# 4Bit_Computer_-_2_4Bit_Input.net
KiCad netlist of a schematic drawn in EAGLE
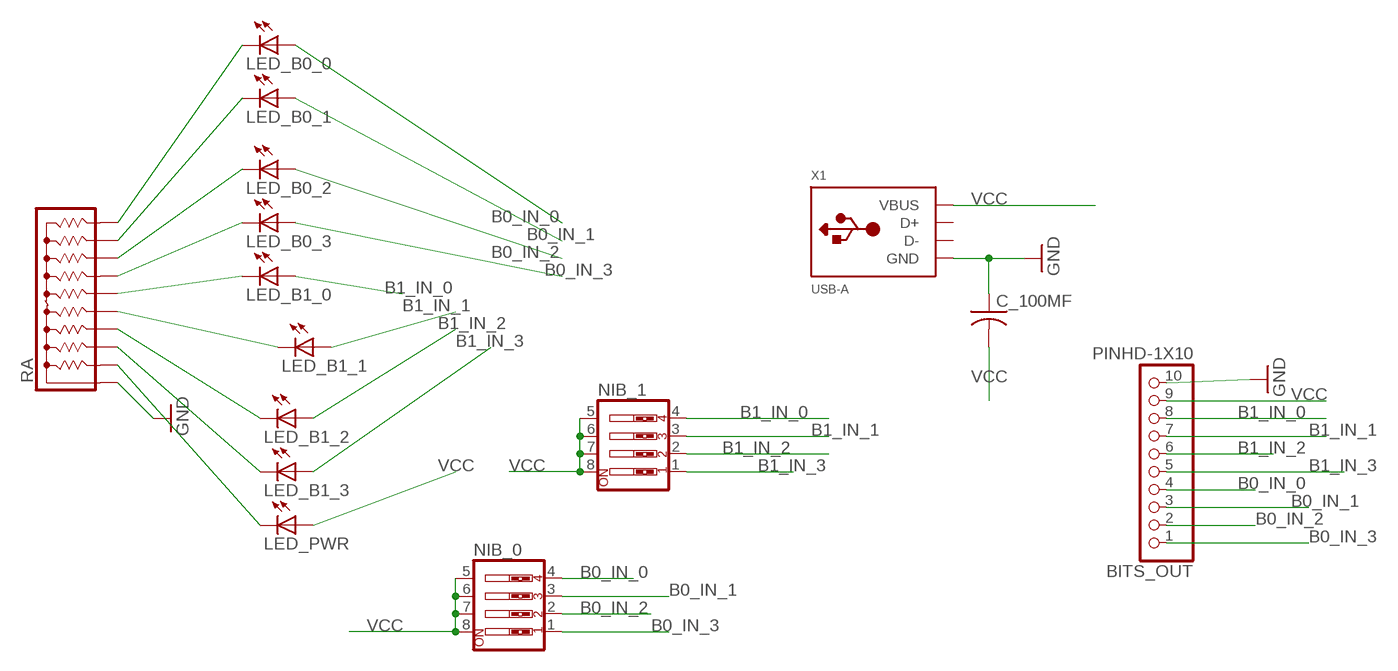
[diagram p0: schematic, sheet 1]

(export (version "E")
  (design (tool "Eeschema 10.0.6"))
  (components
    (comp (ref "BITS_OUT")
      (value "PINHD-1X10")
      (footprint "eagle-import:1X10-BIG")
      (libsource (lib "eagle-import") (part "PINHD-1X10"))
    )
    (comp (ref "C_100MF")
      (value "C-US025-030X050")
      (footprint "eagle-import:C025-030X050")
      (libsource (lib "eagle-import") (part "C-US025-030X050"))
    )
    (comp (ref "LED_B0_0")
      (value "LEDSMT1206")
      (footprint "eagle-import:1206")
      (libsource (lib "eagle-import") (part "LEDSMT1206"))
    )
    (comp (ref "LED_B0_1")
      (value "LEDSMT1206")
      (footprint "eagle-import:1206")
      (libsource (lib "eagle-import") (part "LEDSMT1206"))
    )
    (comp (ref "LED_B0_2")
      (value "LEDSMT1206")
      (footprint "eagle-import:1206")
      (libsource (lib "eagle-import") (part "LEDSMT1206"))
    )
    (comp (ref "LED_B0_3")
      (value "LEDSMT1206")
      (footprint "eagle-import:1206")
      (libsource (lib "eagle-import") (part "LEDSMT1206"))
    )
    (comp (ref "LED_B1_0")
      (value "LEDSMT1206")
      (footprint "eagle-import:1206")
      (libsource (lib "eagle-import") (part "LEDSMT1206"))
    )
    (comp (ref "LED_B1_1")
      (value "LEDSMT1206")
      (footprint "eagle-import:1206")
      (libsource (lib "eagle-import") (part "LEDSMT1206"))
    )
    (comp (ref "LED_B1_2")
      (value "LEDSMT1206")
      (footprint "eagle-import:1206")
      (libsource (lib "eagle-import") (part "LEDSMT1206"))
    )
    (comp (ref "LED_B1_3")
      (value "LEDSMT1206")
      (footprint "eagle-import:1206")
      (libsource (lib "eagle-import") (part "LEDSMT1206"))
    )
    (comp (ref "LED_PWR")
      (value "LEDSMT1206")
      (footprint "eagle-import:1206")
      (libsource (lib "eagle-import") (part "LEDSMT1206"))
    )
    (comp (ref "NIB_0")
      (value "SW_DIP-4")
      (footprint "eagle-import:EDG-04")
      (libsource (lib "eagle-import") (part "SW_DIP-4"))
    )
    (comp (ref "NIB_1")
      (value "SW_DIP-4")
      (footprint "eagle-import:EDG-04")
      (libsource (lib "eagle-import") (part "SW_DIP-4"))
    )
    (comp (ref "RA")
      (value "4610X")
      (footprint "eagle-import:SIP10")
      (libsource (lib "eagle-import") (part "4610X"))
    )
    (comp (ref "X1")
      (value "USB-A")
      (footprint "eagle-import:MOLEX_480371000")
      (libsource (lib "eagle-import") (part "USB-A"))
    )
  )
  (nets
    (net (code "1") (name "/B0_IN_0") (class "Default")
      (node (ref "BITS_OUT") (pin "4") (pinfunction "4_4") (pintype "passive"))
      (node (ref "LED_B0_0") (pin "A") (pinfunction "A_A") (pintype "passive"))
      (node (ref "NIB_0") (pin "4") (pinfunction "4_4") (pintype "passive"))
    )
    (net (code "2") (name "/B0_IN_1") (class "Default")
      (node (ref "BITS_OUT") (pin "3") (pinfunction "3_3") (pintype "passive"))
      (node (ref "LED_B0_1") (pin "A") (pinfunction "A_A") (pintype "passive"))
      (node (ref "NIB_0") (pin "3") (pinfunction "3_3") (pintype "passive"))
    )
    (net (code "3") (name "/B0_IN_2") (class "Default")
      (node (ref "BITS_OUT") (pin "2") (pinfunction "2_2") (pintype "passive"))
      (node (ref "LED_B0_2") (pin "A") (pinfunction "A_A") (pintype "passive"))
      (node (ref "NIB_0") (pin "2") (pinfunction "2_2") (pintype "passive"))
    )
    (net (code "4") (name "/B0_IN_3") (class "Default")
      (node (ref "BITS_OUT") (pin "1") (pinfunction "1_1") (pintype "passive"))
      (node (ref "LED_B0_3") (pin "A") (pinfunction "A_A") (pintype "passive"))
      (node (ref "NIB_0") (pin "1") (pinfunction "1_1") (pintype "passive"))
    )
    (net (code "5") (name "/B1_IN_0") (class "Default")
      (node (ref "BITS_OUT") (pin "8") (pinfunction "8_8") (pintype "passive"))
      (node (ref "LED_B1_0") (pin "A") (pinfunction "A_A") (pintype "passive"))
      (node (ref "NIB_1") (pin "4") (pinfunction "4_4") (pintype "passive"))
    )
    (net (code "6") (name "/B1_IN_1") (class "Default")
      (node (ref "BITS_OUT") (pin "7") (pinfunction "7_7") (pintype "passive"))
      (node (ref "LED_B1_1") (pin "A") (pinfunction "A_A") (pintype "passive"))
      (node (ref "NIB_1") (pin "3") (pinfunction "3_3") (pintype "passive"))
    )
    (net (code "7") (name "/B1_IN_2") (class "Default")
      (node (ref "BITS_OUT") (pin "6") (pinfunction "6_6") (pintype "passive"))
      (node (ref "LED_B1_2") (pin "A") (pinfunction "A_A") (pintype "passive"))
      (node (ref "NIB_1") (pin "2") (pinfunction "2_2") (pintype "passive"))
    )
    (net (code "8") (name "/B1_IN_3") (class "Default")
      (node (ref "BITS_OUT") (pin "5") (pinfunction "5_5") (pintype "passive"))
      (node (ref "LED_B1_3") (pin "A") (pinfunction "A_A") (pintype "passive"))
      (node (ref "NIB_1") (pin "1") (pinfunction "1_1") (pintype "passive"))
    )
    (net (code "9") (name "/VCC") (class "Default")
      (node (ref "BITS_OUT") (pin "9") (pinfunction "9_9") (pintype "passive"))
      (node (ref "C_100MF") (pin "2") (pinfunction "2_2") (pintype "passive"))
      (node (ref "LED_PWR") (pin "A") (pinfunction "A_A") (pintype "passive"))
      (node (ref "NIB_0") (pin "5") (pinfunction "5_5") (pintype "passive"))
      (node (ref "NIB_0") (pin "6") (pinfunction "6_6") (pintype "passive"))
      (node (ref "NIB_0") (pin "7") (pinfunction "7_7") (pintype "passive"))
      (node (ref "NIB_0") (pin "8") (pinfunction "8_8") (pintype "passive"))
      (node (ref "NIB_1") (pin "5") (pinfunction "5_5") (pintype "passive"))
      (node (ref "NIB_1") (pin "6") (pinfunction "6_6") (pintype "passive"))
      (node (ref "NIB_1") (pin "7") (pinfunction "7_7") (pintype "passive"))
      (node (ref "NIB_1") (pin "8") (pinfunction "8_8") (pintype "passive"))
      (node (ref "X1") (pin "1") (pinfunction "VBUS_1") (pintype "power_in"))
    )
    (net (code "10") (name "GND") (class "Default")
      (node (ref "BITS_OUT") (pin "10") (pinfunction "10_10") (pintype "passive"))
      (node (ref "C_100MF") (pin "1") (pinfunction "1_1") (pintype "passive"))
      (node (ref "RA") (pin "1") (pinfunction "1_1") (pintype "passive"))
      (node (ref "X1") (pin "4") (pinfunction "GND_4") (pintype "power_in"))
    )
    (net (code "11") (name "Net-(LED_B0_0-PadC)") (class "Default")
      (node (ref "LED_B0_0") (pin "C") (pinfunction "C_C") (pintype "passive"))
      (node (ref "RA") (pin "10") (pinfunction "10_10") (pintype "passive"))
    )
    (net (code "12") (name "Net-(LED_B0_1-PadC)") (class "Default")
      (node (ref "LED_B0_1") (pin "C") (pinfunction "C_C") (pintype "passive"))
      (node (ref "RA") (pin "9") (pinfunction "9_9") (pintype "passive"))
    )
    (net (code "13") (name "Net-(LED_B0_2-PadC)") (class "Default")
      (node (ref "LED_B0_2") (pin "C") (pinfunction "C_C") (pintype "passive"))
      (node (ref "RA") (pin "8") (pinfunction "8_8") (pintype "passive"))
    )
    (net (code "14") (name "Net-(LED_B0_3-PadC)") (class "Default")
      (node (ref "LED_B0_3") (pin "C") (pinfunction "C_C") (pintype "passive"))
      (node (ref "RA") (pin "7") (pinfunction "7_7") (pintype "passive"))
    )
    (net (code "15") (name "Net-(LED_B1_0-PadC)") (class "Default")
      (node (ref "LED_B1_0") (pin "C") (pinfunction "C_C") (pintype "passive"))
      (node (ref "RA") (pin "6") (pinfunction "6_6") (pintype "passive"))
    )
    (net (code "16") (name "Net-(LED_B1_1-PadC)") (class "Default")
      (node (ref "LED_B1_1") (pin "C") (pinfunction "C_C") (pintype "passive"))
      (node (ref "RA") (pin "5") (pinfunction "5_5") (pintype "passive"))
    )
    (net (code "17") (name "Net-(LED_B1_2-PadC)") (class "Default")
      (node (ref "LED_B1_2") (pin "C") (pinfunction "C_C") (pintype "passive"))
      (node (ref "RA") (pin "4") (pinfunction "4_4") (pintype "passive"))
    )
    (net (code "18") (name "Net-(LED_B1_3-PadC)") (class "Default")
      (node (ref "LED_B1_3") (pin "C") (pinfunction "C_C") (pintype "passive"))
      (node (ref "RA") (pin "3") (pinfunction "3_3") (pintype "passive"))
    )
    (net (code "19") (name "Net-(LED_PWR-PadC)") (class "Default")
      (node (ref "LED_PWR") (pin "C") (pinfunction "C_C") (pintype "passive"))
      (node (ref "RA") (pin "2") (pinfunction "2_2") (pintype "passive"))
    )
    (net (code "20") (name "unconnected-(X1-D+-Pad3)") (class "Default")
      (node (ref "X1") (pin "3") (pinfunction "D+_3") (pintype "bidirectional"))
    )
    (net (code "21") (name "unconnected-(X1-D--Pad2)") (class "Default")
      (node (ref "X1") (pin "2") (pinfunction "D-_2") (pintype "bidirectional"))
    )
  )
)
